# seths_4layer_nano.net
KiCad netlist of a schematic drawn in EAGLE
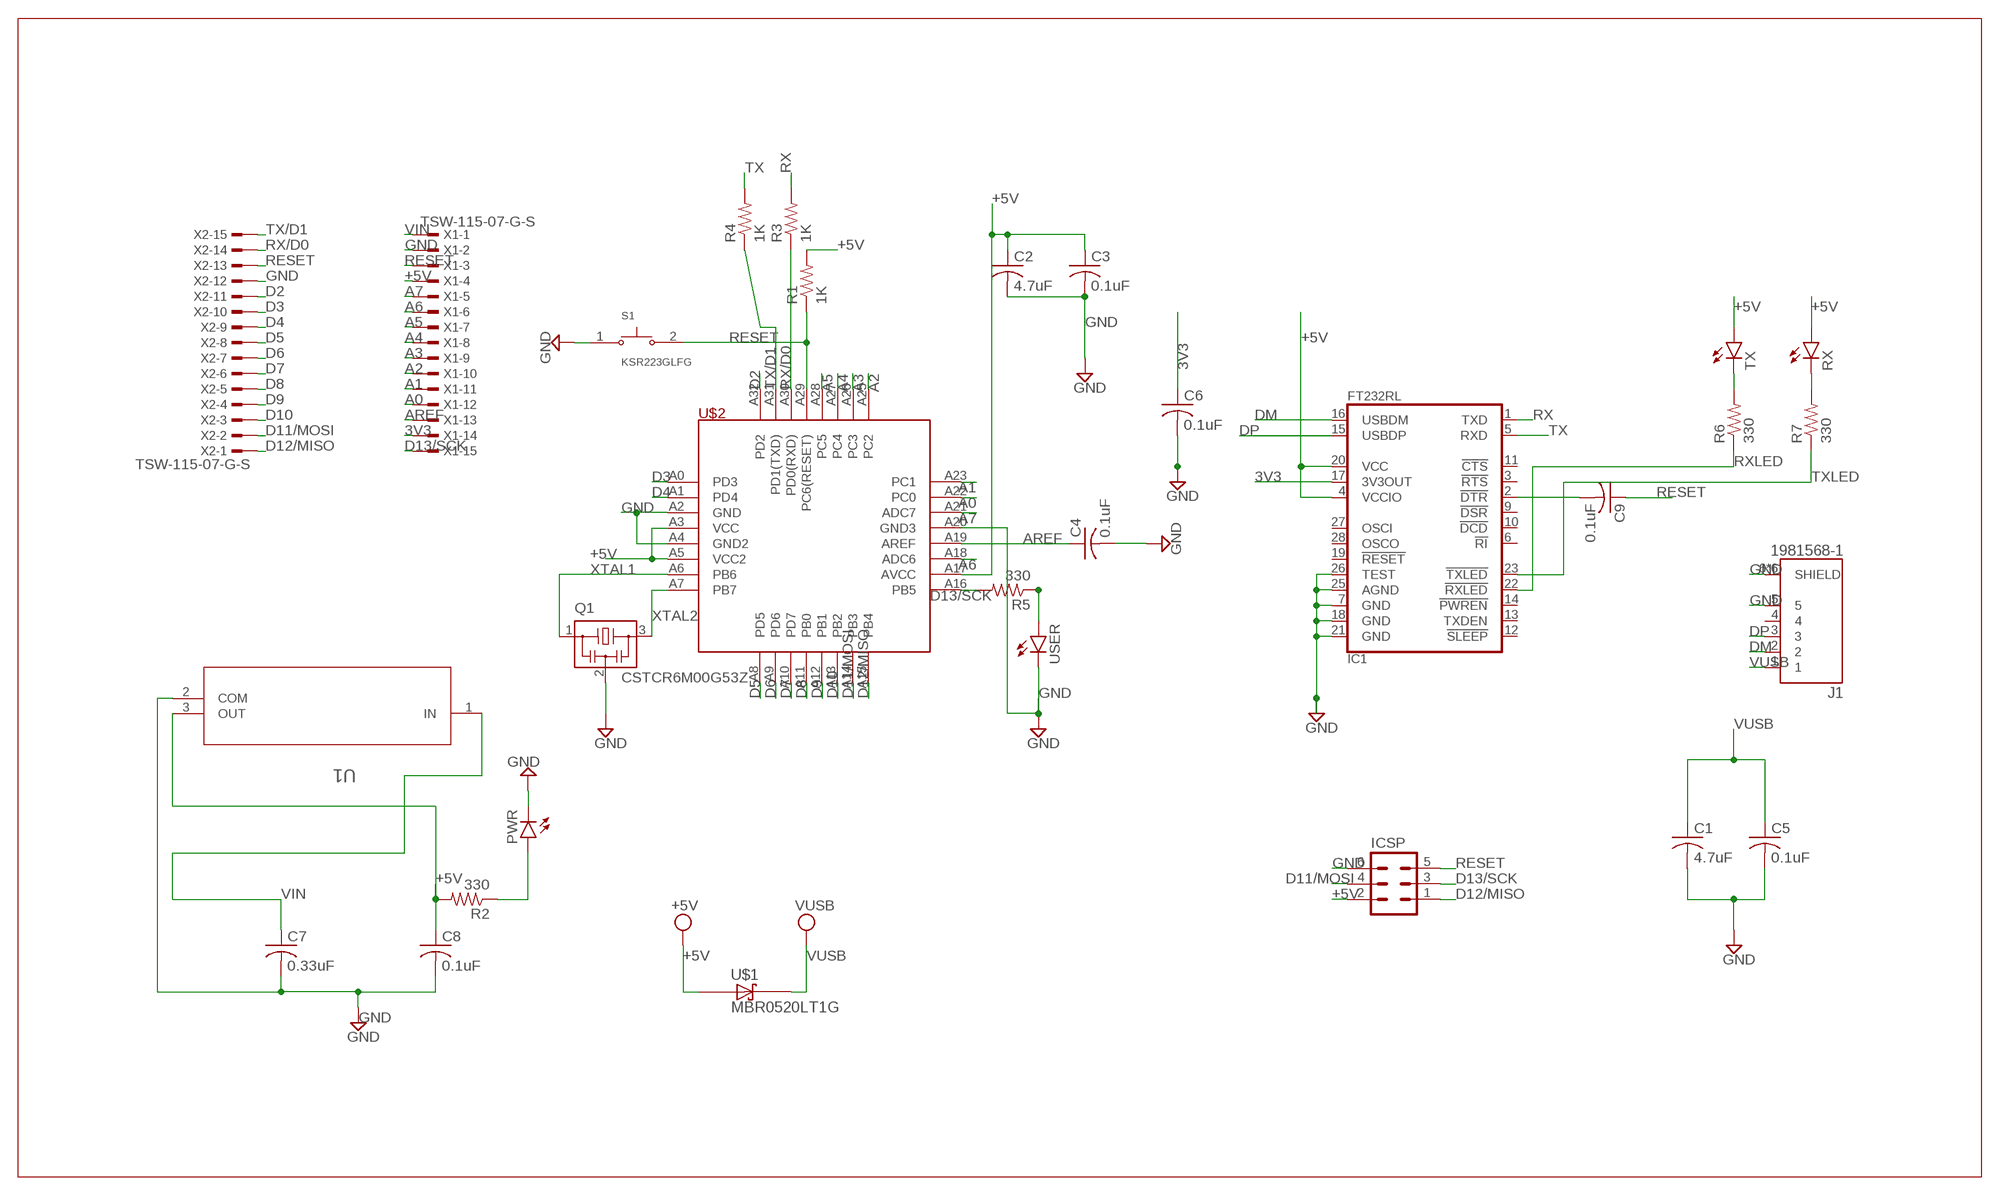
[diagram p0: schematic, sheet 1]

(export (version "E")
  (design (tool "Eeschema 10.0.6"))
  (components
    (comp (ref "C1")
      (value "4.7uF")
      (footprint "eagle-import:C1206")
      (libsource (lib "eagle-import") (part "C-USC1206"))
    )
    (comp (ref "C2")
      (value "4.7uF")
      (footprint "eagle-import:C1206")
      (libsource (lib "eagle-import") (part "C-USC1206"))
    )
    (comp (ref "C3")
      (value "0.1uF")
      (footprint "eagle-import:C0603")
      (libsource (lib "eagle-import") (part "C-USC0603"))
    )
    (comp (ref "C4")
      (value "0.1uF")
      (footprint "eagle-import:C0603")
      (libsource (lib "eagle-import") (part "C-USC0603"))
    )
    (comp (ref "C5")
      (value "0.1uF")
      (footprint "eagle-import:C0603")
      (libsource (lib "eagle-import") (part "C-USC0603"))
    )
    (comp (ref "C6")
      (value "0.1uF")
      (footprint "eagle-import:C0603")
      (libsource (lib "eagle-import") (part "C-USC0603"))
    )
    (comp (ref "C7")
      (value "0.33uF")
      (footprint "eagle-import:C0603")
      (libsource (lib "eagle-import") (part "C-USC0603"))
    )
    (comp (ref "C8")
      (value "0.1uF")
      (footprint "eagle-import:C0603")
      (libsource (lib "eagle-import") (part "C-USC0603"))
    )
    (comp (ref "C9")
      (value "0.1uF")
      (footprint "eagle-import:C0603")
      (libsource (lib "eagle-import") (part "C-USC0603"))
    )
    (comp (ref "IC1")
      (value "FT232RL")
      (footprint "eagle-import:SSOP28-LD")
      (fields (field (name "MF") "FTDI, Future"))
      (libsource (lib "eagle-import") (part "FT232RL"))
    )
    (comp (ref "ICSP")
      (value "MA03-2")
      (footprint "eagle-import:MA03-2")
      (libsource (lib "eagle-import") (part "MA03-2"))
    )
    (comp (ref "J1")
      (value "1981568-1")
      (footprint "eagle-import:TE_1981568-1")
      (fields (field (name "MF") "TE Connectivity") (field (name "MP") "19815681"))
      (libsource (lib "eagle-import") (part "1981568-1"))
    )
    (comp (ref "PWR")
      (value "RED_POWER")
      (footprint "eagle-import:CHIP-LED0603")
      (libsource (lib "eagle-import") (part "LEDCHIP-LED0603"))
    )
    (comp (ref "Q1")
      (value "CSTCR6M00G53Z")
      (footprint "eagle-import:CSTCR6M")
      (fields (field (name "MPN") "CSTCR6M00G53-R0"))
      (libsource (lib "eagle-import") (part "CSTCR6M00G53Z"))
    )
    (comp (ref "R1")
      (value "1K")
      (footprint "eagle-import:R0603")
      (libsource (lib "eagle-import") (part "R-US_R0603"))
    )
    (comp (ref "R2")
      (value "330")
      (footprint "eagle-import:R0603")
      (libsource (lib "eagle-import") (part "R-US_R0603"))
    )
    (comp (ref "R3")
      (value "1K")
      (footprint "eagle-import:R0603")
      (libsource (lib "eagle-import") (part "R-US_R0603"))
    )
    (comp (ref "R4")
      (value "1K")
      (footprint "eagle-import:R0603")
      (libsource (lib "eagle-import") (part "R-US_R0603"))
    )
    (comp (ref "R5")
      (value "330")
      (footprint "eagle-import:R0603")
      (libsource (lib "eagle-import") (part "R-US_R0603"))
    )
    (comp (ref "R6")
      (value "330")
      (footprint "eagle-import:R0603")
      (libsource (lib "eagle-import") (part "R-US_R0603"))
    )
    (comp (ref "R7")
      (value "330")
      (footprint "eagle-import:R0603")
      (libsource (lib "eagle-import") (part "R-US_R0603"))
    )
    (comp (ref "RX")
      (value "RED_TX")
      (footprint "eagle-import:CHIP-LED0603")
      (libsource (lib "eagle-import") (part "LEDCHIP-LED0603"))
    )
    (comp (ref "S1")
      (value "KSR223GLFG")
      (footprint "eagle-import:SW_KSR223GLFG")
      (fields (field (name "MF") "C&K"))
      (libsource (lib "eagle-import") (part "KSR223GLFG"))
    )
    (comp (ref "TX")
      (value "RED_RX")
      (footprint "eagle-import:CHIP-LED0603")
      (libsource (lib "eagle-import") (part "LEDCHIP-LED0603"))
    )
    (comp (ref "U$1")
      (value "MBR0520LT1G")
      (footprint "eagle-import:SOD3716X117(SOD-123)")
      (fields (field (name "MF") "ON Semiconductor"))
      (libsource (lib "eagle-import") (part "MBR0520LT1G"))
    )
    (comp (ref "U$2")
      (value "ATMEGA328P")
      (footprint "eagle-import:TQFP32")
      (libsource (lib "eagle-import") (part "ATMEGA328P"))
    )
    (comp (ref "U1")
      (value "UA78M05CDCYRDCY4-L")
      (footprint "eagle-import:DCY4-L")
      (fields (field (name "MANUFACTURER_PART_NUMBER") "UA78M05CDCYR"))
      (libsource (lib "eagle-import") (part "UA78M05CDCYRDCY4-L"))
    )
    (comp (ref "USER")
      (value "Amber_L")
      (footprint "eagle-import:CHIP-LED0603")
      (libsource (lib "eagle-import") (part "LEDCHIP-LED0603"))
    )
    (comp (ref "X1")
      (value "TSW-115-07-G-S")
      (footprint "eagle-import:TSW-115-XX-G-S")
      (fields (field (name "MF") "Samtec Inc."))
      (libsource (lib "eagle-import") (part "TSW-115--G-S07"))
    )
    (comp (ref "X2")
      (value "TSW-115-07-G-S")
      (footprint "eagle-import:TSW-115-XX-G-S")
      (fields (field (name "MF") "Samtec Inc."))
      (libsource (lib "eagle-import") (part "TSW-115--G-S07"))
    )
  )
  (nets
    (net (code "1") (name "+5V") (class "Default")
      (node (ref "C2") (pin "1") (pinfunction "1_1") (pintype "passive"))
      (node (ref "C3") (pin "1") (pinfunction "1_1") (pintype "passive"))
      (node (ref "C8") (pin "1") (pinfunction "1_1") (pintype "passive"))
      (node (ref "IC1") (pin "20") (pinfunction "VCC_20") (pintype "power_in"))
      (node (ref "IC1") (pin "4") (pinfunction "VCCIO_4") (pintype "power_in"))
      (node (ref "ICSP") (pin "2") (pinfunction "2_2") (pintype "passive"))
      (node (ref "R1") (pin "2") (pinfunction "2_2") (pintype "passive"))
      (node (ref "R2") (pin "2") (pinfunction "2_2") (pintype "passive"))
      (node (ref "RX") (pin "A") (pinfunction "A_A") (pintype "passive"))
      (node (ref "TX") (pin "A") (pinfunction "A_A") (pintype "passive"))
      (node (ref "U$1") (pin "2") (pinfunction "A_2") (pintype "passive"))
      (node (ref "U$2") (pin "A17") (pinfunction "AVCC_A17") (pintype "bidirectional"))
      (node (ref "U$2") (pin "A3") (pinfunction "VCC_A3") (pintype "bidirectional"))
      (node (ref "U$2") (pin "A5") (pinfunction "VCC2_A5") (pintype "bidirectional"))
      (node (ref "U1") (pin "3") (pinfunction "OUT_3") (pintype "input"))
      (node (ref "X1") (pin "4") (pinfunction "1_4") (pintype "passive"))
    )
    (net (code "2") (name "/3V3") (class "Default")
      (node (ref "C6") (pin "1") (pinfunction "1_1") (pintype "passive"))
      (node (ref "IC1") (pin "17") (pinfunction "3V3OUT_17") (pintype "power_in"))
      (node (ref "X1") (pin "14") (pinfunction "1_14") (pintype "passive"))
    )
    (net (code "3") (name "/A0") (class "Default")
      (node (ref "U$2") (pin "A22") (pinfunction "PC0_A22") (pintype "bidirectional"))
      (node (ref "X1") (pin "12") (pinfunction "1_12") (pintype "passive"))
    )
    (net (code "4") (name "/A1") (class "Default")
      (node (ref "U$2") (pin "A23") (pinfunction "PC1_A23") (pintype "bidirectional"))
      (node (ref "X1") (pin "11") (pinfunction "1_11") (pintype "passive"))
    )
    (net (code "5") (name "/A2") (class "Default")
      (node (ref "U$2") (pin "A25") (pinfunction "PC2_A25") (pintype "bidirectional"))
      (node (ref "X1") (pin "10") (pinfunction "1_10") (pintype "passive"))
    )
    (net (code "6") (name "/A3") (class "Default")
      (node (ref "U$2") (pin "A26") (pinfunction "PC3_A26") (pintype "bidirectional"))
      (node (ref "X1") (pin "9") (pinfunction "1_9") (pintype "passive"))
    )
    (net (code "7") (name "/A4") (class "Default")
      (node (ref "U$2") (pin "A27") (pinfunction "PC4_A27") (pintype "bidirectional"))
      (node (ref "X1") (pin "8") (pinfunction "1_8") (pintype "passive"))
    )
    (net (code "8") (name "/A5") (class "Default")
      (node (ref "U$2") (pin "A28") (pinfunction "PC5_A28") (pintype "bidirectional"))
      (node (ref "X1") (pin "7") (pinfunction "1_7") (pintype "passive"))
    )
    (net (code "9") (name "/A6") (class "Default")
      (node (ref "U$2") (pin "A18") (pinfunction "ADC6_A18") (pintype "bidirectional"))
      (node (ref "X1") (pin "6") (pinfunction "1_6") (pintype "passive"))
    )
    (net (code "10") (name "/A7") (class "Default")
      (node (ref "U$2") (pin "A21") (pinfunction "ADC7_A21") (pintype "bidirectional"))
      (node (ref "X1") (pin "5") (pinfunction "1_5") (pintype "passive"))
    )
    (net (code "11") (name "/AREF") (class "Default")
      (node (ref "C4") (pin "1") (pinfunction "1_1") (pintype "passive"))
      (node (ref "U$2") (pin "A19") (pinfunction "AREF_A19") (pintype "bidirectional"))
      (node (ref "X1") (pin "13") (pinfunction "1_13") (pintype "passive"))
    )
    (net (code "12") (name "/D2") (class "Default")
      (node (ref "U$2") (pin "A32") (pinfunction "PD2_A32") (pintype "bidirectional"))
      (node (ref "X2") (pin "11") (pinfunction "1_11") (pintype "passive"))
    )
    (net (code "13") (name "/D3") (class "Default")
      (node (ref "U$2") (pin "A0") (pinfunction "PD3_A0") (pintype "bidirectional"))
      (node (ref "X2") (pin "10") (pinfunction "1_10") (pintype "passive"))
    )
    (net (code "14") (name "/D4") (class "Default")
      (node (ref "U$2") (pin "A1") (pinfunction "PD4_A1") (pintype "bidirectional"))
      (node (ref "X2") (pin "9") (pinfunction "1_9") (pintype "passive"))
    )
    (net (code "15") (name "/D5") (class "Default")
      (node (ref "U$2") (pin "A8") (pinfunction "PD5_A8") (pintype "bidirectional"))
      (node (ref "X2") (pin "8") (pinfunction "1_8") (pintype "passive"))
    )
    (net (code "16") (name "/D6") (class "Default")
      (node (ref "U$2") (pin "A9") (pinfunction "PD6_A9") (pintype "bidirectional"))
      (node (ref "X2") (pin "7") (pinfunction "1_7") (pintype "passive"))
    )
    (net (code "17") (name "/D7") (class "Default")
      (node (ref "U$2") (pin "A10") (pinfunction "PD7_A10") (pintype "bidirectional"))
      (node (ref "X2") (pin "6") (pinfunction "1_6") (pintype "passive"))
    )
    (net (code "18") (name "/D8") (class "Default")
      (node (ref "U$2") (pin "A11") (pinfunction "PB0_A11") (pintype "bidirectional"))
      (node (ref "X2") (pin "5") (pinfunction "1_5") (pintype "passive"))
    )
    (net (code "19") (name "/D9") (class "Default")
      (node (ref "U$2") (pin "A12") (pinfunction "PB1_A12") (pintype "bidirectional"))
      (node (ref "X2") (pin "4") (pinfunction "1_4") (pintype "passive"))
    )
    (net (code "20") (name "/D10") (class "Default")
      (node (ref "U$2") (pin "A13") (pinfunction "PB2_A13") (pintype "bidirectional"))
      (node (ref "X2") (pin "3") (pinfunction "1_3") (pintype "passive"))
    )
    (net (code "21") (name "/D11{slash}MOSI") (class "Default")
      (node (ref "ICSP") (pin "4") (pinfunction "4_4") (pintype "passive"))
      (node (ref "U$2") (pin "A14") (pinfunction "PB3_A14") (pintype "bidirectional"))
      (node (ref "X2") (pin "2") (pinfunction "1_2") (pintype "passive"))
    )
    (net (code "22") (name "/D12{slash}MISO") (class "Default")
      (node (ref "ICSP") (pin "1") (pinfunction "1_1") (pintype "passive"))
      (node (ref "U$2") (pin "A15") (pinfunction "PB4_A15") (pintype "bidirectional"))
      (node (ref "X2") (pin "1") (pinfunction "1_1") (pintype "passive"))
    )
    (net (code "23") (name "/D13{slash}SCK") (class "Default")
      (node (ref "ICSP") (pin "3") (pinfunction "3_3") (pintype "passive"))
      (node (ref "R5") (pin "2") (pinfunction "2_2") (pintype "passive"))
      (node (ref "U$2") (pin "A16") (pinfunction "PB5_A16") (pintype "bidirectional"))
      (node (ref "X1") (pin "15") (pinfunction "1_15") (pintype "passive"))
    )
    (net (code "24") (name "/DM") (class "Default")
      (node (ref "IC1") (pin "16") (pinfunction "USBDM_16") (pintype "bidirectional"))
      (node (ref "J1") (pin "2") (pinfunction "2_2") (pintype "passive"))
    )
    (net (code "25") (name "/DP") (class "Default")
      (node (ref "IC1") (pin "15") (pinfunction "USBDP_15") (pintype "bidirectional"))
      (node (ref "J1") (pin "3") (pinfunction "3_3") (pintype "passive"))
    )
    (net (code "26") (name "/RESET") (class "Default")
      (node (ref "C9") (pin "1") (pinfunction "1_1") (pintype "passive"))
      (node (ref "ICSP") (pin "5") (pinfunction "5_5") (pintype "passive"))
      (node (ref "R1") (pin "1") (pinfunction "1_1") (pintype "passive"))
      (node (ref "S1") (pin "2") (pinfunction "2_2") (pintype "passive"))
      (node (ref "U$2") (pin "A29") (pinfunction "PC6(RESET)_A29") (pintype "bidirectional"))
      (node (ref "X1") (pin "3") (pinfunction "1_3") (pintype "passive"))
      (node (ref "X2") (pin "13") (pinfunction "1_13") (pintype "passive"))
    )
    (net (code "27") (name "/RX") (class "Default")
      (node (ref "IC1") (pin "1") (pinfunction "TXD_1") (pintype "output"))
      (node (ref "R3") (pin "2") (pinfunction "2_2") (pintype "passive"))
    )
    (net (code "28") (name "/RXLED") (class "Default")
      (node (ref "IC1") (pin "22") (pinfunction "~{RXLED}_22") (pintype "input"))
      (node (ref "R6") (pin "1") (pinfunction "1_1") (pintype "passive"))
    )
    (net (code "29") (name "/RX{slash}D0") (class "Default")
      (node (ref "R3") (pin "1") (pinfunction "1_1") (pintype "passive"))
      (node (ref "U$2") (pin "A30") (pinfunction "PD0(RXD)_A30") (pintype "bidirectional"))
      (node (ref "X2") (pin "14") (pinfunction "1_14") (pintype "passive"))
    )
    (net (code "30") (name "/TX") (class "Default")
      (node (ref "IC1") (pin "5") (pinfunction "RXD_5") (pintype "input"))
      (node (ref "R4") (pin "2") (pinfunction "2_2") (pintype "passive"))
    )
    (net (code "31") (name "/TXLED") (class "Default")
      (node (ref "IC1") (pin "23") (pinfunction "~{TXLED}_23") (pintype "input"))
      (node (ref "R7") (pin "1") (pinfunction "1_1") (pintype "passive"))
    )
    (net (code "32") (name "/TX{slash}D1") (class "Default")
      (node (ref "R4") (pin "1") (pinfunction "1_1") (pintype "passive"))
      (node (ref "U$2") (pin "A31") (pinfunction "PD1(TXD)_A31") (pintype "bidirectional"))
      (node (ref "X2") (pin "15") (pinfunction "1_15") (pintype "passive"))
    )
    (net (code "33") (name "/VIN") (class "Default")
      (node (ref "C7") (pin "1") (pinfunction "1_1") (pintype "passive"))
      (node (ref "U1") (pin "1") (pinfunction "IN_1") (pintype "output"))
      (node (ref "X1") (pin "1") (pinfunction "1_1") (pintype "passive"))
    )
    (net (code "34") (name "/XTAL1") (class "Default")
      (node (ref "Q1") (pin "1") (pinfunction "1_1") (pintype "passive"))
      (node (ref "U$2") (pin "A6") (pinfunction "PB6_A6") (pintype "bidirectional"))
    )
    (net (code "35") (name "/XTAL2") (class "Default")
      (node (ref "Q1") (pin "3") (pinfunction "3_3") (pintype "passive"))
      (node (ref "U$2") (pin "A7") (pinfunction "PB7_A7") (pintype "bidirectional"))
    )
    (net (code "36") (name "GND") (class "Default")
      (node (ref "C1") (pin "2") (pinfunction "2_2") (pintype "passive"))
      (node (ref "C2") (pin "2") (pinfunction "2_2") (pintype "passive"))
      (node (ref "C3") (pin "2") (pinfunction "2_2") (pintype "passive"))
      (node (ref "C4") (pin "2") (pinfunction "2_2") (pintype "passive"))
      (node (ref "C5") (pin "2") (pinfunction "2_2") (pintype "passive"))
      (node (ref "C6") (pin "2") (pinfunction "2_2") (pintype "passive"))
      (node (ref "C7") (pin "2") (pinfunction "2_2") (pintype "passive"))
      (node (ref "C8") (pin "2") (pinfunction "2_2") (pintype "passive"))
      (node (ref "IC1") (pin "18") (pinfunction "GND_18") (pintype "power_in"))
      (node (ref "IC1") (pin "21") (pinfunction "GND_21") (pintype "power_in"))
      (node (ref "IC1") (pin "25") (pinfunction "AGND_25") (pintype "power_in"))
      (node (ref "IC1") (pin "26") (pinfunction "TEST_26") (pintype "input"))
      (node (ref "IC1") (pin "7") (pinfunction "GND_7") (pintype "power_in"))
      (node (ref "ICSP") (pin "6") (pinfunction "6_6") (pintype "passive"))
      (node (ref "J1") (pin "10") (pinfunction "SHIELD_10") (pintype "passive"))
      (node (ref "J1") (pin "11") (pinfunction "SHIELD_11") (pintype "passive"))
      (node (ref "J1") (pin "5") (pinfunction "5_5") (pintype "passive"))
      (node (ref "J1") (pin "6") (pinfunction "SHIELD_6") (pintype "passive"))
      (node (ref "J1") (pin "7") (pinfunction "SHIELD_7") (pintype "passive"))
      (node (ref "J1") (pin "8") (pinfunction "SHIELD_8") (pintype "passive"))
      (node (ref "J1") (pin "9") (pinfunction "SHIELD_9") (pintype "passive"))
      (node (ref "PWR") (pin "C") (pinfunction "C_C") (pintype "passive"))
      (node (ref "Q1") (pin "2") (pinfunction "2_2") (pintype "passive"))
      (node (ref "S1") (pin "1") (pinfunction "1_1") (pintype "passive"))
      (node (ref "U$2") (pin "A2") (pinfunction "GND_A2") (pintype "bidirectional"))
      (node (ref "U$2") (pin "A20") (pinfunction "GND3_A20") (pintype "bidirectional"))
      (node (ref "U$2") (pin "A4") (pinfunction "GND2_A4") (pintype "bidirectional"))
      (node (ref "U1") (pin "2") (pinfunction "COM_2") (pintype "power_in"))
      (node (ref "USER") (pin "C") (pinfunction "C_C") (pintype "passive"))
      (node (ref "X1") (pin "2") (pinfunction "1_2") (pintype "passive"))
      (node (ref "X2") (pin "12") (pinfunction "1_12") (pintype "passive"))
    )
    (net (code "37") (name "Net-(IC1-~{DTR})") (class "Default")
      (node (ref "C9") (pin "2") (pinfunction "2_2") (pintype "passive"))
      (node (ref "IC1") (pin "2") (pinfunction "~{DTR}_2") (pintype "output"))
    )
    (net (code "38") (name "Net-(PWR-PadA)") (class "Default")
      (node (ref "PWR") (pin "A") (pinfunction "A_A") (pintype "passive"))
      (node (ref "R2") (pin "1") (pinfunction "1_1") (pintype "passive"))
    )
    (net (code "39") (name "Net-(R5-Pad1)") (class "Default")
      (node (ref "R5") (pin "1") (pinfunction "1_1") (pintype "passive"))
      (node (ref "USER") (pin "A") (pinfunction "A_A") (pintype "passive"))
    )
    (net (code "40") (name "Net-(R6-Pad2)") (class "Default")
      (node (ref "R6") (pin "2") (pinfunction "2_2") (pintype "passive"))
      (node (ref "TX") (pin "C") (pinfunction "C_C") (pintype "passive"))
    )
    (net (code "41") (name "Net-(R7-Pad2)") (class "Default")
      (node (ref "R7") (pin "2") (pinfunction "2_2") (pintype "passive"))
      (node (ref "RX") (pin "C") (pinfunction "C_C") (pintype "passive"))
    )
    (net (code "42") (name "VUSB") (class "Default")
      (node (ref "C1") (pin "1") (pinfunction "1_1") (pintype "passive"))
      (node (ref "C5") (pin "1") (pinfunction "1_1") (pintype "passive"))
      (node (ref "J1") (pin "1") (pinfunction "1_1") (pintype "passive"))
      (node (ref "U$1") (pin "1") (pinfunction "C_1") (pintype "passive"))
    )
    (net (code "43") (name "unconnected-(IC1-OSCI-Pad27)") (class "Default")
      (node (ref "IC1") (pin "27") (pinfunction "OSCI_27") (pintype "no_connect"))
    )
    (net (code "44") (name "unconnected-(IC1-OSCO-Pad28)") (class "Default")
      (node (ref "IC1") (pin "28") (pinfunction "OSCO_28") (pintype "output"))
    )
    (net (code "45") (name "unconnected-(IC1-TXDEN-Pad13)") (class "Default")
      (node (ref "IC1") (pin "13") (pinfunction "TXDEN_13") (pintype "no_connect"))
    )
    (net (code "46") (name "unconnected-(IC1-~{CTS}-Pad11)") (class "Default")
      (node (ref "IC1") (pin "11") (pinfunction "~{CTS}_11") (pintype "input"))
    )
    (net (code "47") (name "unconnected-(IC1-~{DCD}-Pad10)") (class "Default")
      (node (ref "IC1") (pin "10") (pinfunction "~{DCD}_10") (pintype "no_connect"))
    )
    (net (code "48") (name "unconnected-(IC1-~{DSR}-Pad9)") (class "Default")
      (node (ref "IC1") (pin "9") (pinfunction "~{DSR}_9") (pintype "no_connect"))
    )
    (net (code "49") (name "unconnected-(IC1-~{PWREN}-Pad14)") (class "Default")
      (node (ref "IC1") (pin "14") (pinfunction "~{PWREN}_14") (pintype "no_connect"))
    )
    (net (code "50") (name "unconnected-(IC1-~{RESET}-Pad19)") (class "Default")
      (node (ref "IC1") (pin "19") (pinfunction "~{RESET}_19") (pintype "no_connect"))
    )
    (net (code "51") (name "unconnected-(IC1-~{RI}-Pad6)") (class "Default")
      (node (ref "IC1") (pin "6") (pinfunction "~{RI}_6") (pintype "no_connect"))
    )
    (net (code "52") (name "unconnected-(IC1-~{RTS}-Pad3)") (class "Default")
      (node (ref "IC1") (pin "3") (pinfunction "~{RTS}_3") (pintype "output"))
    )
    (net (code "53") (name "unconnected-(IC1-~{SLEEP}-Pad12)") (class "Default")
      (node (ref "IC1") (pin "12") (pinfunction "~{SLEEP}_12") (pintype "no_connect"))
    )
    (net (code "54") (name "unconnected-(J1-Pad4)") (class "Default")
      (node (ref "J1") (pin "4") (pinfunction "4_4") (pintype "passive"))
    )
  )
)
